# P08_KEY_BOOT_SET.net
KiCad netlist of a schematic drawn in Altium Designer
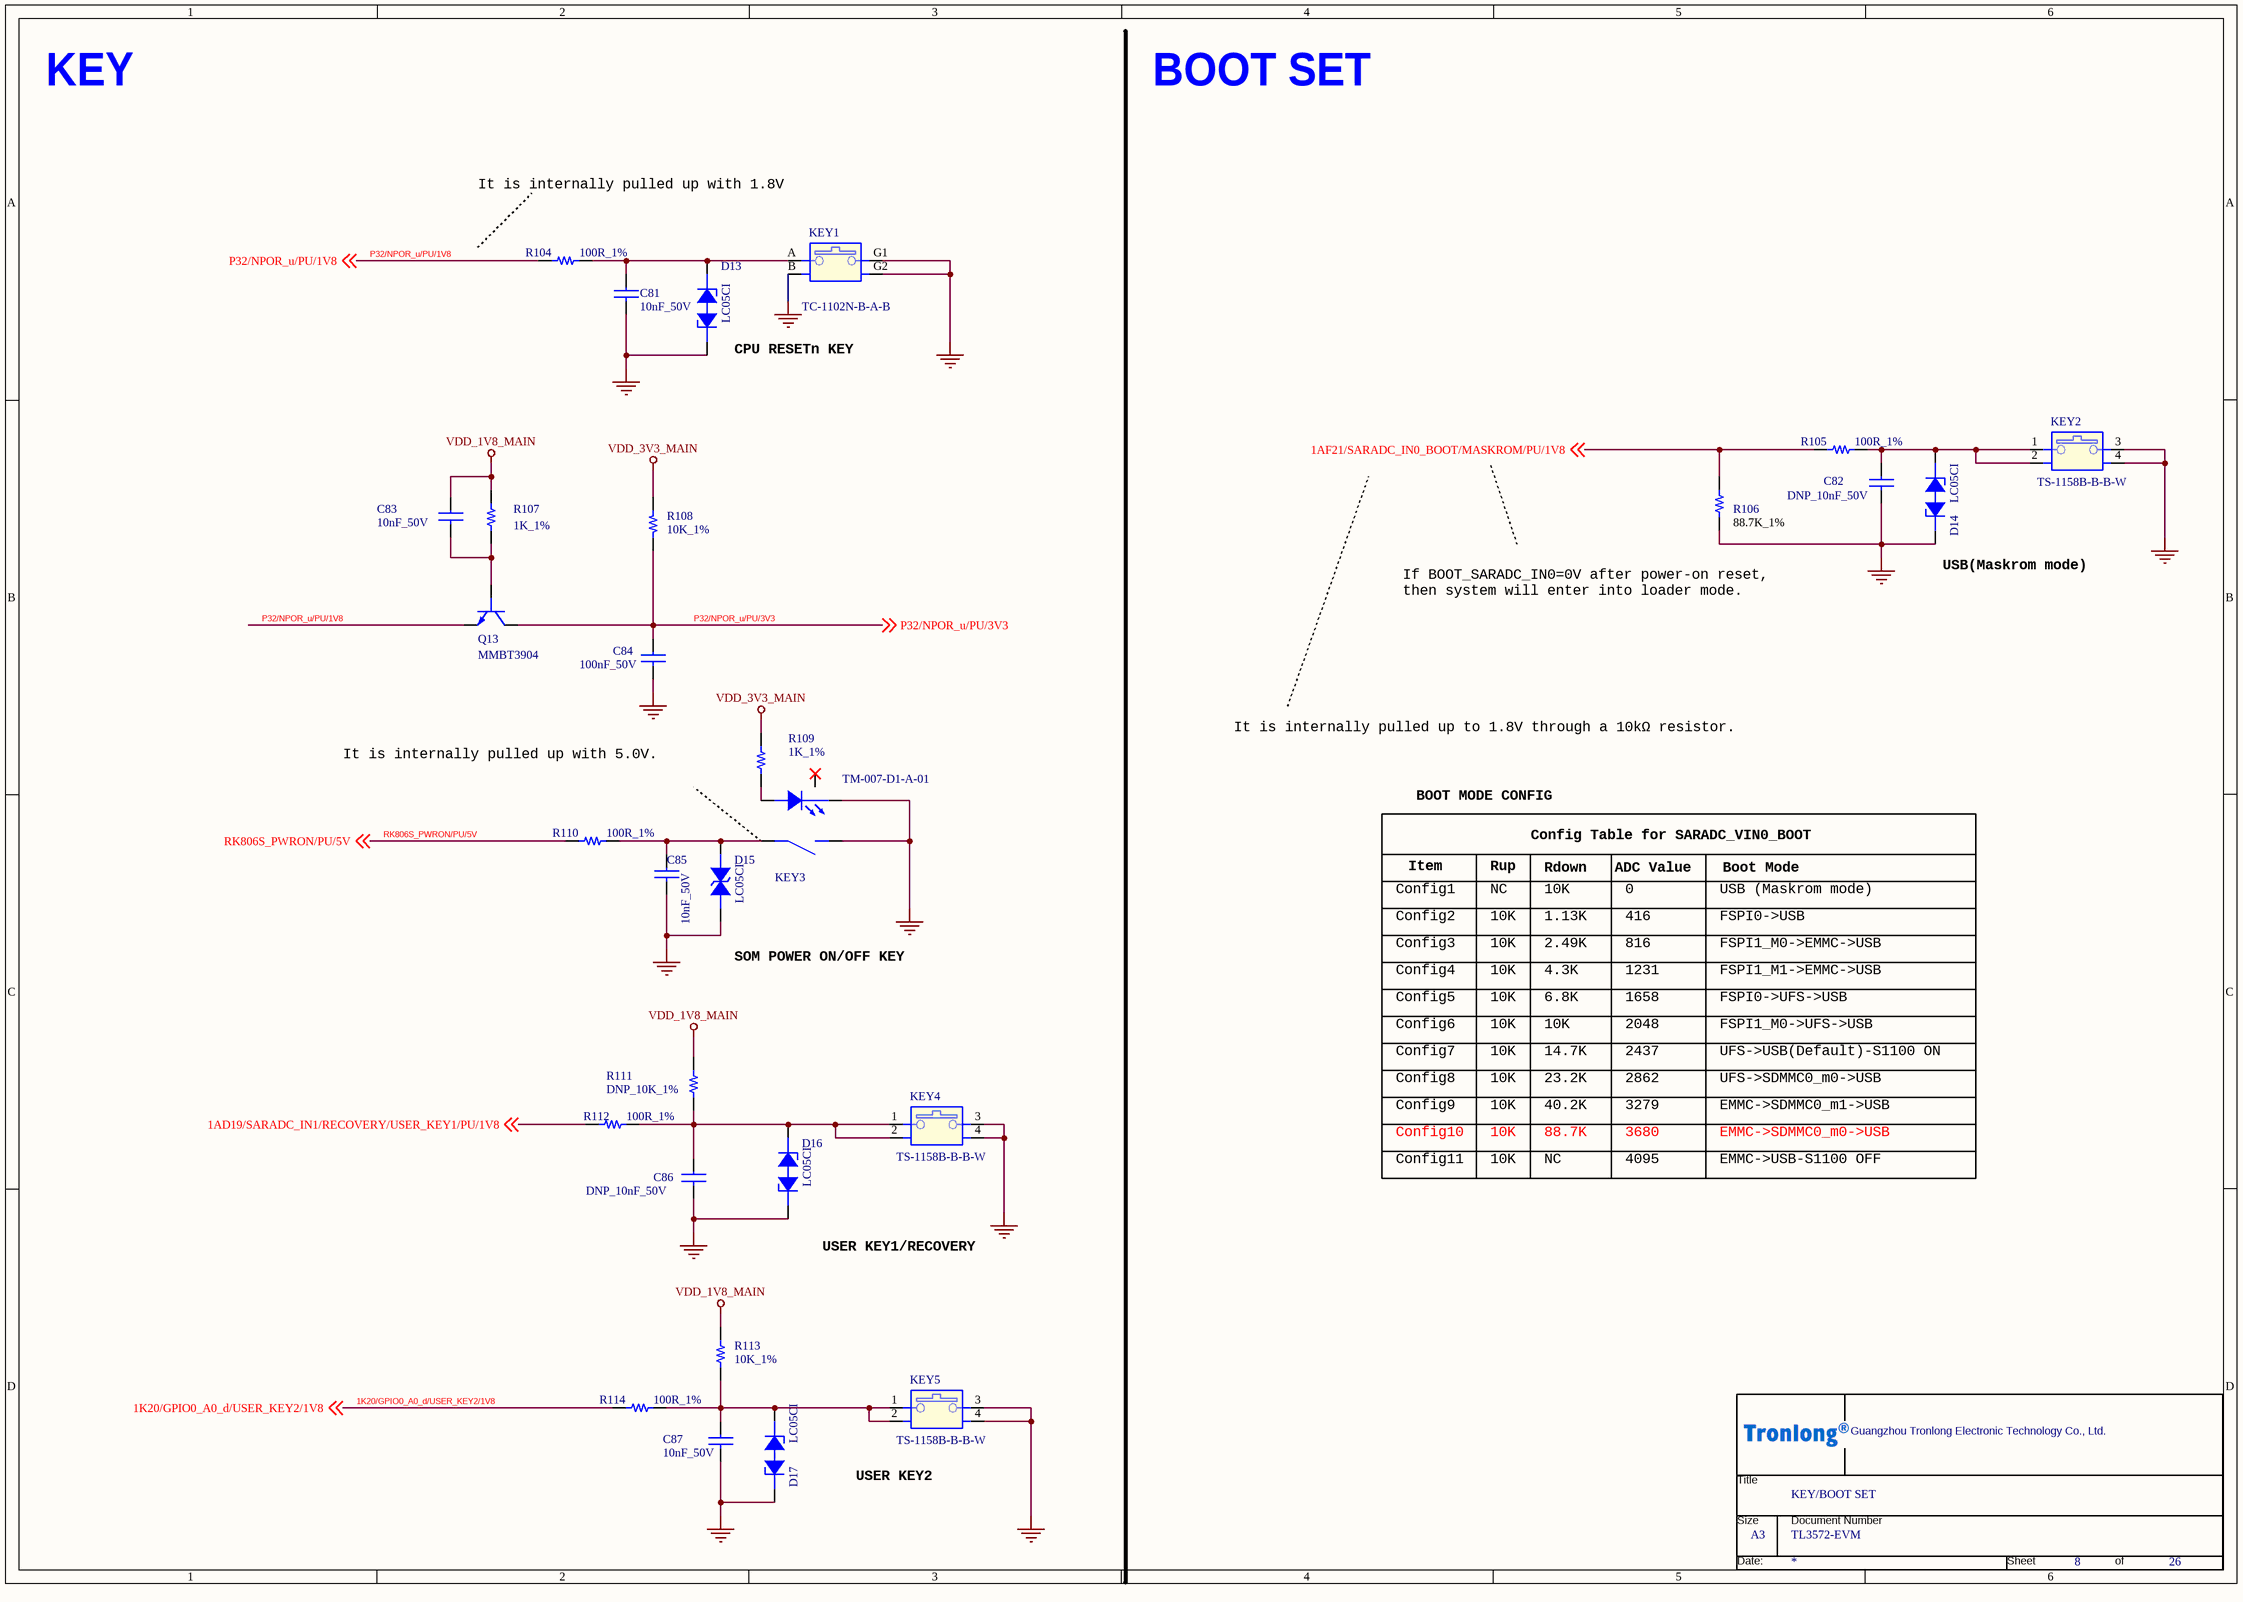
[diagram p0: P08_KEY_BOOT SET.SchDoc]

(export (version "E")
  (design (tool "Eeschema 10.0.6"))
  (components
    (comp (ref "C81")
      (value "10nF_50V")
      (footprint "C0402")
      (description "贴片陶瓷电容,10nF,10%,50V,X7R")
      (fields
        (field (name "MANUFACTURER PARTNUMBER") "0402B103K500NT")
        (field (name "MANUFACTURER") "广东风华高新科技股份有限公司（FH）")
      )
      (libsource (lib "*") (part "CAP NP_Dup3"))
    )
    (comp (ref "C82")
      (value "DNP_10nF_50V")
      (footprint "C0402")
      (description "贴片陶瓷电容,10nF,10%,50V,X7R")
      (fields
        (field (name "MANUFACTURER PARTNUMBER") "0402B103K500NT")
        (field (name "MANUFACTURER") "广东风华高新科技股份有限公司（FH）")
      )
      (libsource (lib "*") (part "CAP NP_Dup3"))
    )
    (comp (ref "C83")
      (value "10nF_50V")
      (footprint "C0402")
      (description "贴片陶瓷电容,10nF,10%,50V,X7R")
      (fields
        (field (name "MANUFACTURER") "广东风华高新科技股份有限公司（FH）")
        (field (name "MANUFACTURER PARTNUMBER") "0402B103K500NT")
      )
      (libsource (lib "*") (part "CAP NP_Dup3"))
    )
    (comp (ref "C84")
      (value "100nF_50V")
      (footprint "C0402")
      (description "贴片陶瓷电容,100nF,10%,50V,X7R")
      (fields
        (field (name "MANUFACTURER") "广东风华高新科技股份有限公司（FH）")
        (field (name "MANUFACTURER PARTNUMBER") "0402B104K500NT")
      )
      (libsource (lib "*") (part "CAP NP_Dup3"))
    )
    (comp (ref "C85")
      (value "10nF_50V")
      (footprint "C0402")
      (description "贴片陶瓷电容,10nF,10%,50V,X7R")
      (fields
        (field (name "MANUFACTURER") "广东风华高新科技股份有限公司（FH）")
        (field (name "MANUFACTURER PARTNUMBER") "0402B103K500NT")
      )
      (libsource (lib "*") (part "CAP NP_Dup3"))
    )
    (comp (ref "C86")
      (value "DNP_10nF_50V")
      (footprint "C0402")
      (description "贴片陶瓷电容,10nF,10%,50V,X7R")
      (fields
        (field (name "MANUFACTURER") "广东风华高新科技股份有限公司（FH）")
        (field (name "MANUFACTURER PARTNUMBER") "0402B103K500NT")
      )
      (libsource (lib "*") (part "CAP NP_Dup3"))
    )
    (comp (ref "C87")
      (value "10nF_50V")
      (footprint "C0402")
      (description "贴片陶瓷电容,10nF,10%,50V,X7R")
      (fields
        (field (name "MANUFACTURER") "广东风华高新科技股份有限公司（FH）")
        (field (name "MANUFACTURER PARTNUMBER") "0402B103K500NT")
      )
      (libsource (lib "*") (part "CAP NP_Dup3"))
    )
    (comp (ref "D13")
      (value "LC05CI")
      (footprint "SOD323")
      (description "TVS二极管,VRWM=5V,VBR=6V,一组,双向,30KV,30KV")
      (fields (field (name "MANUFACTURER") "上海雷卯电子科技有限公司（Leiditech）"))
      (libsource (lib "*") (part "DIODE BREAKDOWN_2"))
    )
    (comp (ref "D14")
      (value "LC05CI")
      (footprint "SOD323")
      (description "TVS二极管,VRWM=5V,VBR=6V,一组,双向,30KV,30KV")
      (fields (field (name "MANUFACTURER") "上海雷卯电子科技有限公司（Leiditech）"))
      (libsource (lib "*") (part "DIODE BREAKDOWN_2"))
    )
    (comp (ref "D15")
      (value "LC05CI")
      (footprint "SOD323")
      (description "TVS二极管,VRWM=5V,VBR=6V,一组,双向,30KV,30KV")
      (fields (field (name "MANUFACTURER") "上海雷卯电子科技有限公司（Leiditech）"))
      (libsource (lib "*") (part "DIODE-BI"))
    )
    (comp (ref "D16")
      (value "LC05CI")
      (footprint "SOD323")
      (description "TVS二极管,VRWM=5V,VBR=6V,一组,双向,30KV,30KV")
      (fields (field (name "MANUFACTURER") "上海雷卯电子科技有限公司（Leiditech）"))
      (libsource (lib "*") (part "DIODE BREAKDOWN_2"))
    )
    (comp (ref "D17")
      (value "LC05CI")
      (footprint "SOD323")
      (description "TVS二极管,VRWM=5V,VBR=6V,一组,双向,30KV,30KV")
      (fields (field (name "MANUFACTURER") "上海雷卯电子科技有限公司（Leiditech）"))
      (libsource (lib "*") (part "DIODE BREAKDOWN_2"))
    )
    (comp (ref "KEY1")
      (value "TC-1102N-B-A-B")
      (footprint "sw_evq-pf003m")
      (description "插件侧按按键,4P,90,黑色,H=7mm,带支架")
      (fields (field (name "MANUFACTURER") "广东星坤科技股份有限公司（XKB）"))
      (libsource (lib "*") (part "SW PUSHBUTTON-SPST SHIELD_3"))
    )
    (comp (ref "KEY2")
      (value "TS-1158B-B-B-W")
      (footprint "TS-1158B-B-B-W")
      (description "贴片按键,4P,180,白色,H=3.5mm")
      (fields (field (name "MANUFACTURER") "广东星坤科技股份有限公司（XKB）"))
      (libsource (lib "*") (part "SW PUSHBUTTON-SPST SHIELD_0"))
    )
    (comp (ref "KEY3")
      (value "TM-007-D1-A-01")
      (footprint "sw-th_xkb_tm-007-d1-a-01")
      (description "插件侧按按键,4P,90,白色,H=8.7,带灯")
      (fields (field (name "MANUFACTURER") "广东星坤科技股份有限公司（XKB）"))
      (libsource (lib "*") (part "LED_5"))
    )
    (comp (ref "KEY4")
      (value "TS-1158B-B-B-W")
      (footprint "TS-1158B-B-B-W")
      (description "贴片按键,4P,180,白色,H=3.5mm")
      (fields (field (name "MANUFACTURER") "广东星坤科技股份有限公司（XKB）"))
      (libsource (lib "*") (part "SW PUSHBUTTON-SPST SHIELD_0"))
    )
    (comp (ref "KEY5")
      (value "TS-1158B-B-B-W")
      (footprint "TS-1158B-B-B-W")
      (description "贴片按键,4P,180,白色,H=3.5mm")
      (fields (field (name "MANUFACTURER") "广东星坤科技股份有限公司（XKB）"))
      (libsource (lib "*") (part "SW PUSHBUTTON-SPST SHIELD_0"))
    )
    (comp (ref "Q13")
      (value "MMBT3904")
      (footprint "SOT23-3_DBZ3")
      (description "BJT,NPN,Vceo=40V,Ic=200mA,fT=300MHz,PD=200mW")
      (fields (field (name "MANUFACTURER") "江苏长晶科技股份有限公司（JSCJ）"))
      (libsource (lib "*") (part "MMBT3904/SOT"))
    )
    (comp (ref "R104")
      (value "100R_1%")
      (footprint "R0402")
      (description "贴片电阻,100R,±1%,1/16W")
      (fields
        (field (name "MANUFACTURER PARTNUMBER") "RC-02K1000FT")
        (field (name "MANUFACTURER") "广东风华高新科技股份有限公司（FH）")
      )
      (libsource (lib "*") (part "Resistor_Dup4"))
    )
    (comp (ref "R105")
      (value "100R_1%")
      (footprint "R0402")
      (description "贴片电阻,100R,±1%,1/16W")
      (fields
        (field (name "MANUFACTURER PARTNUMBER") "RC-02K1000FT")
        (field (name "MANUFACTURER") "广东风华高新科技股份有限公司（FH）")
      )
      (libsource (lib "*") (part "Resistor_Dup4"))
    )
    (comp (ref "R106")
      (value "88.7K_1%")
      (footprint "R0402")
      (description "贴片电阻,88.7K,±1%,1/16W")
      (fields
        (field (name "MANUFACTURER PARTNUMBER") "RC-02K8872FT")
        (field (name "MANUFACTURER") "广东风华高新科技股份有限公司（FH）")
        (field (name "CREATED BY") "JJJ")
      )
      (libsource (lib "*") (part "Resistor_Dup1"))
    )
    (comp (ref "R107")
      (value "1K_1%")
      (footprint "R0402")
      (description "贴片电阻,0R,±1%,1/16W")
      (fields
        (field (name "MANUFACTURER PARTNUMBER") "RC-02000FT")
        (field (name "MANUFACTURER") "广东风华高新科技股份有限公司（FH）")
      )
      (libsource (lib "*") (part "Resistor_Dup4"))
    )
    (comp (ref "R108")
      (value "10K_1%")
      (footprint "R0402")
      (description "贴片电阻,10K,±1%,1/16W")
      (fields
        (field (name "MANUFACTURER PARTNUMBER") "RC-02K1002FT")
        (field (name "MANUFACTURER") "广东风华高新科技股份有限公司（FH）")
      )
      (libsource (lib "*") (part "Resistor_Dup4"))
    )
    (comp (ref "R109")
      (value "1K_1%")
      (footprint "R0603")
      (description "贴片电阻,1K,±1%,1/10W")
      (fields
        (field (name "MANUFACTURER PARTNUMBER") "RS-03K1001FT")
        (field (name "MANUFACTURER") "广东风华高新科技股份有限公司（FH）")
      )
      (libsource (lib "*") (part "Resistor_Dup4"))
    )
    (comp (ref "R110")
      (value "100R_1%")
      (footprint "R0402")
      (description "贴片电阻,100R,±1%,1/16W")
      (fields
        (field (name "MANUFACTURER PARTNUMBER") "RC-02K1000FT")
        (field (name "MANUFACTURER") "广东风华高新科技股份有限公司（FH）")
      )
      (libsource (lib "*") (part "Resistor_Dup4"))
    )
    (comp (ref "R111")
      (value "DNP_10K_1%")
      (footprint "R0402")
      (description "贴片电阻,10K,±1%,1/16W")
      (fields
        (field (name "MANUFACTURER") "广东风华高新科技股份有限公司（FH）")
        (field (name "MANUFACTURER PARTNUMBER") "RC-02K1002FT")
      )
      (libsource (lib "*") (part "Resistor_Dup4"))
    )
    (comp (ref "R112")
      (value "100R_1%")
      (footprint "R0402")
      (description "贴片电阻,100R,±1%,1/16W")
      (fields
        (field (name "MANUFACTURER PARTNUMBER") "RC-02K1000FT")
        (field (name "MANUFACTURER") "广东风华高新科技股份有限公司（FH）")
      )
      (libsource (lib "*") (part "Resistor_Dup4"))
    )
    (comp (ref "R113")
      (value "10K_1%")
      (footprint "R0402")
      (description "贴片电阻,10K,±1%,1/16W")
      (fields
        (field (name "MANUFACTURER PARTNUMBER") "RC-02K1002FT")
        (field (name "MANUFACTURER") "广东风华高新科技股份有限公司（FH）")
      )
      (libsource (lib "*") (part "Resistor_Dup4"))
    )
    (comp (ref "R114")
      (value "100R_1%")
      (footprint "R0402")
      (description "贴片电阻,100R,±1%,1/16W")
      (fields
        (field (name "MANUFACTURER") "广东风华高新科技股份有限公司（FH）")
        (field (name "MANUFACTURER PARTNUMBER") "RC-02K1000FT")
      )
      (libsource (lib "*") (part "Resistor_Dup4"))
    )
  )
  (nets
    (net (code "1") (name "1AD19{slash}SARADC_IN1{slash}RECOVERY{slash}USER_KEY1{slash}PU{slash}1V8") (class "Default")
      (node (ref "R112") (pin "1") (pinfunction "1_1") (pintype "passive"))
    )
    (net (code "2") (name "1AF21{slash}SARADC_IN0_BOOT{slash}MASKROM{slash}PU{slash}1V8") (class "Default")
      (node (ref "R105") (pin "1") (pinfunction "1_1") (pintype "passive"))
      (node (ref "R106") (pin "1") (pinfunction "1_1") (pintype "passive"))
    )
    (net (code "3") (name "1K20{slash}GPIO0_A0_d{slash}USER_KEY2{slash}1V8") (class "Default")
      (node (ref "R114") (pin "1") (pinfunction "1_1") (pintype "passive"))
    )
    (net (code "4") (name "GND") (class "Default")
      (node (ref "C81") (pin "2") (pinfunction "2_2") (pintype "passive"))
      (node (ref "C82") (pin "2") (pinfunction "2_2") (pintype "passive"))
      (node (ref "C84") (pin "2") (pinfunction "2_2") (pintype "passive"))
      (node (ref "C85") (pin "2") (pinfunction "2_2") (pintype "passive"))
      (node (ref "C86") (pin "2") (pinfunction "2_2") (pintype "passive"))
      (node (ref "C87") (pin "2") (pinfunction "2_2") (pintype "passive"))
      (node (ref "D13") (pin "2") (pinfunction "CATHODE2_2") (pintype "passive"))
      (node (ref "D14") (pin "2") (pinfunction "CATHODE2_2") (pintype "passive"))
      (node (ref "D15") (pin "2") (pinfunction "2_2") (pintype "passive"))
      (node (ref "D16") (pin "2") (pinfunction "CATHODE2_2") (pintype "passive"))
      (node (ref "D17") (pin "2") (pinfunction "CATHODE2_2") (pintype "passive"))
      (node (ref "KEY1") (pin "B") (pinfunction "2_B") (pintype "passive"))
      (node (ref "KEY1") (pin "G1") (pinfunction "3_G1") (pintype "passive"))
      (node (ref "KEY1") (pin "G2") (pinfunction "4_G2") (pintype "passive"))
      (node (ref "KEY2") (pin "3") (pinfunction "3_3") (pintype "passive"))
      (node (ref "KEY2") (pin "4") (pinfunction "4_4") (pintype "passive"))
      (node (ref "KEY3") (pin "2") (pinfunction "2_2") (pintype "passive"))
      (node (ref "KEY3") (pin "3") (pinfunction "CATHODE_3") (pintype "passive"))
      (node (ref "KEY4") (pin "3") (pinfunction "3_3") (pintype "passive"))
      (node (ref "KEY4") (pin "4") (pinfunction "4_4") (pintype "passive"))
      (node (ref "KEY5") (pin "3") (pinfunction "3_3") (pintype "passive"))
      (node (ref "KEY5") (pin "4") (pinfunction "4_4") (pintype "passive"))
      (node (ref "R106") (pin "2") (pinfunction "2_2") (pintype "passive"))
    )
    (net (code "5") (name "Net-(C85-Pad1)") (class "Default")
      (node (ref "C85") (pin "1") (pinfunction "1_1") (pintype "passive"))
      (node (ref "D15") (pin "1") (pinfunction "1_1") (pintype "passive"))
      (node (ref "KEY3") (pin "1") (pinfunction "1_1") (pintype "passive"))
      (node (ref "R110") (pin "2") (pinfunction "2_2") (pintype "passive"))
    )
    (net (code "6") (name "Net-(D13-ANODE1)") (class "Default")
      (node (ref "C81") (pin "1") (pinfunction "1_1") (pintype "passive"))
      (node (ref "D13") (pin "1") (pinfunction "ANODE1_1") (pintype "passive"))
      (node (ref "KEY1") (pin "A") (pinfunction "1_A") (pintype "passive"))
      (node (ref "R104") (pin "2") (pinfunction "2_2") (pintype "passive"))
    )
    (net (code "7") (name "Net-(D14-ANODE1)") (class "Default")
      (node (ref "C82") (pin "1") (pinfunction "1_1") (pintype "passive"))
      (node (ref "D14") (pin "1") (pinfunction "ANODE1_1") (pintype "passive"))
      (node (ref "KEY2") (pin "1") (pinfunction "1_1") (pintype "passive"))
      (node (ref "KEY2") (pin "2") (pinfunction "2_2") (pintype "passive"))
      (node (ref "R105") (pin "2") (pinfunction "2_2") (pintype "passive"))
    )
    (net (code "8") (name "Net-(D16-ANODE1)") (class "Default")
      (node (ref "C86") (pin "1") (pinfunction "1_1") (pintype "passive"))
      (node (ref "D16") (pin "1") (pinfunction "ANODE1_1") (pintype "passive"))
      (node (ref "KEY4") (pin "1") (pinfunction "1_1") (pintype "passive"))
      (node (ref "KEY4") (pin "2") (pinfunction "2_2") (pintype "passive"))
      (node (ref "R111") (pin "1") (pinfunction "1_1") (pintype "passive"))
      (node (ref "R112") (pin "2") (pinfunction "2_2") (pintype "passive"))
    )
    (net (code "9") (name "Net-(D17-ANODE1)") (class "Default")
      (node (ref "C87") (pin "1") (pinfunction "1_1") (pintype "passive"))
      (node (ref "D17") (pin "1") (pinfunction "ANODE1_1") (pintype "passive"))
      (node (ref "KEY5") (pin "1") (pinfunction "1_1") (pintype "passive"))
      (node (ref "KEY5") (pin "2") (pinfunction "2_2") (pintype "passive"))
      (node (ref "R113") (pin "1") (pinfunction "1_1") (pintype "passive"))
      (node (ref "R114") (pin "2") (pinfunction "2_2") (pintype "passive"))
    )
    (net (code "10") (name "Net-(KEY3-ANODE)") (class "Default")
      (node (ref "KEY3") (pin "4") (pinfunction "ANODE_4") (pintype "passive"))
      (node (ref "R109") (pin "2") (pinfunction "2_2") (pintype "passive"))
    )
    (net (code "11") (name "Net-(Q13-B)") (class "Default")
      (node (ref "C83") (pin "2") (pinfunction "2_2") (pintype "passive"))
      (node (ref "Q13") (pin "1") (pinfunction "B_1") (pintype "passive"))
      (node (ref "R107") (pin "2") (pinfunction "2_2") (pintype "passive"))
    )
    (net (code "12") (name "P32{slash}NPOR_u{slash}PU{slash}1V8") (class "Default")
      (node (ref "Q13") (pin "2") (pinfunction "E_2") (pintype "passive"))
      (node (ref "R104") (pin "1") (pinfunction "1_1") (pintype "passive"))
    )
    (net (code "13") (name "P32{slash}NPOR_u{slash}PU{slash}3V3") (class "Default")
      (node (ref "C84") (pin "1") (pinfunction "1_1") (pintype "passive"))
      (node (ref "Q13") (pin "3") (pinfunction "C_3") (pintype "passive"))
      (node (ref "R108") (pin "2") (pinfunction "2_2") (pintype "passive"))
    )
    (net (code "14") (name "RK806S_PWRON{slash}PU{slash}5V") (class "Default")
      (node (ref "R110") (pin "1") (pinfunction "1_1") (pintype "passive"))
    )
    (net (code "15") (name "VDD_1V8_MAIN") (class "Default")
      (node (ref "C83") (pin "1") (pinfunction "1_1") (pintype "passive"))
      (node (ref "R107") (pin "1") (pinfunction "1_1") (pintype "passive"))
      (node (ref "R111") (pin "2") (pinfunction "2_2") (pintype "passive"))
      (node (ref "R113") (pin "2") (pinfunction "2_2") (pintype "passive"))
    )
    (net (code "16") (name "VDD_3V3_MAIN") (class "Default")
      (node (ref "R108") (pin "1") (pinfunction "1_1") (pintype "passive"))
      (node (ref "R109") (pin "1") (pinfunction "1_1") (pintype "passive"))
    )
    (net (code "17") (name "unconnected-(KEY3-NPTH-Pad5)") (class "Default")
      (node (ref "KEY3") (pin "5") (pinfunction "NPTH_5") (pintype "passive+no_connect"))
    )
  )
)
